# Sheet1.net
KiCad netlist of a schematic drawn in Altium Designer
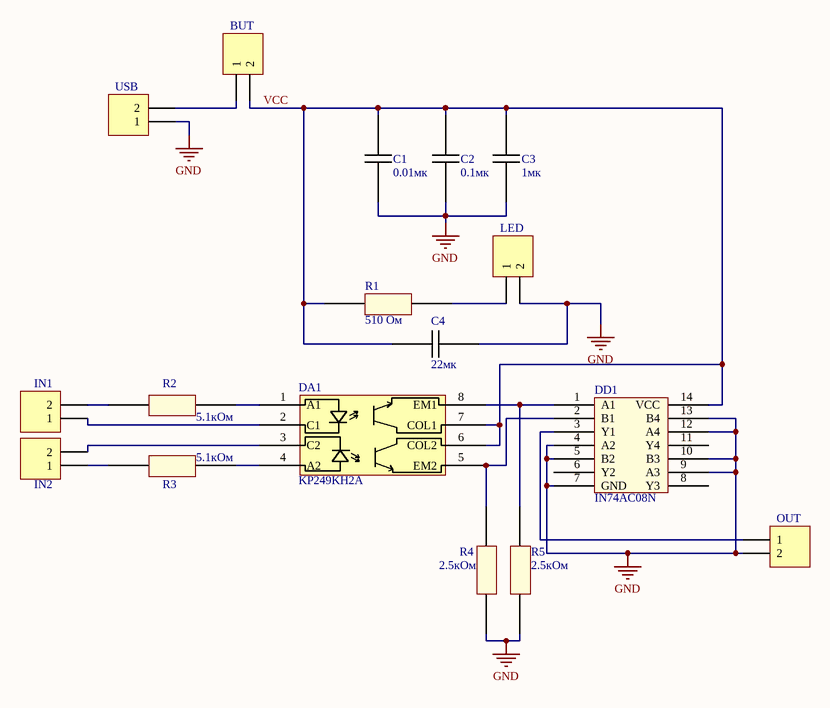
[diagram p0: Sheet1.SchDoc]

(export (version "E")
  (design (tool "Eeschema 10.0.6"))
  (components
    (comp (ref "C1") (value "0.01мк") (footprint "RES 0805") (libsource (lib "msp_SchLib") (part "CAP")))
    (comp (ref "C2") (value "0.1мк") (footprint "RES 0805") (libsource (lib "msp_SchLib") (part "CAP")))
    (comp (ref "C3") (value "1мк") (footprint "RES 0805") (libsource (lib "msp_SchLib") (part "CAP")))
    (comp (ref "C4") (value "22мк") (footprint "RES 0805") (libsource (lib "msp_SchLib") (part "CAP")))
    (comp (ref "DA1")
      (value "KP249KH2A")
      (footprint "SCS-8")
      (libsource (lib "msp_SchLib") (part "KP249KH2A"))
    )
    (comp (ref "DD1")
      (value "IN74AC08N")
      (footprint "SCS-14")
      (libsource (lib "msp_SchLib") (part "IN74AC08N"))
    )
    (comp (ref "P1")
      (value "BUT")
      (footprint "HDR1X2")
      (description "Header, 2-Pin")
      (fields (field (name "PUBLISHER") "Altium Limited"))
      (libsource (lib "Miscellaneous Connectors") (part "Header 2"))
    )
    (comp (ref "P2")
      (value "USB")
      (footprint "HDR1X2")
      (description "Header, 2-Pin")
      (fields (field (name "PUBLISHER") "Altium Limited"))
      (libsource (lib "") (part "Header 2_1"))
    )
    (comp (ref "P3")
      (value "LED")
      (footprint "HDR1X2")
      (description "Header, 2-Pin")
      (fields (field (name "PUBLISHER") "Altium Limited"))
      (libsource (lib "Miscellaneous Connectors") (part "Header 2"))
    )
    (comp (ref "P4")
      (value "IN2")
      (footprint "HDR1X2")
      (description "Header, 2-Pin")
      (fields (field (name "PUBLISHER") "Altium Limited"))
      (libsource (lib "") (part "Header 2_1"))
    )
    (comp (ref "P5")
      (value "IN1")
      (footprint "HDR1X2")
      (description "Header, 2-Pin")
      (fields (field (name "PUBLISHER") "Altium Limited"))
      (libsource (lib "") (part "Header 2_1"))
    )
    (comp (ref "P6")
      (value "OUT")
      (footprint "HDR1X2")
      (description "Header, 2-Pin")
      (fields (field (name "PUBLISHER") "Altium Limited"))
      (libsource (lib "") (part "Header 2_2"))
    )
    (comp (ref "R1") (value "510 Ом") (footprint "RES 0805") (libsource (lib "msp_SchLib") (part "RES")))
    (comp (ref "R2") (value "5.1кОм") (footprint "RES 0805") (libsource (lib "msp_SchLib") (part "RES")))
    (comp (ref "R3") (value "5.1кОм") (footprint "RES 0805") (libsource (lib "msp_SchLib") (part "RES")))
    (comp (ref "R4") (value "2.5кОм") (footprint "RES 0805") (libsource (lib "") (part "RES_1")))
    (comp (ref "R5") (value "2.5кОм") (footprint "RES 0805") (libsource (lib "") (part "RES_1")))
  )
  (nets
    (net (code "1") (name "/VCC") (class "Default")
      (node (ref "C1") (pin "2") (pinfunction "2_2") (pintype "passive"))
      (node (ref "C2") (pin "2") (pinfunction "2_2") (pintype "passive"))
      (node (ref "C3") (pin "2") (pinfunction "2_2") (pintype "passive"))
      (node (ref "C4") (pin "2") (pinfunction "2_2") (pintype "passive"))
      (node (ref "DA1") (pin "6") (pinfunction "COL2_6") (pintype "passive"))
      (node (ref "DA1") (pin "7") (pinfunction "COL1_7") (pintype "passive"))
      (node (ref "DD1") (pin "14") (pinfunction "VCC_14") (pintype "passive"))
      (node (ref "P1") (pin "2") (pinfunction "2_2") (pintype "passive"))
      (node (ref "R1") (pin "1") (pinfunction "1_1") (pintype "passive"))
    )
    (net (code "2") (name "GND") (class "Default")
      (node (ref "C1") (pin "1") (pinfunction "1_1") (pintype "passive"))
      (node (ref "C2") (pin "1") (pinfunction "1_1") (pintype "passive"))
      (node (ref "C3") (pin "1") (pinfunction "1_1") (pintype "passive"))
      (node (ref "C4") (pin "1") (pinfunction "1_1") (pintype "passive"))
      (node (ref "DD1") (pin "10") (pinfunction "B3_10") (pintype "passive"))
      (node (ref "DD1") (pin "12") (pinfunction "A4_12") (pintype "passive"))
      (node (ref "DD1") (pin "13") (pinfunction "B4_13") (pintype "passive"))
      (node (ref "DD1") (pin "4") (pinfunction "A2_4") (pintype "passive"))
      (node (ref "DD1") (pin "5") (pinfunction "B2_5") (pintype "passive"))
      (node (ref "DD1") (pin "7") (pinfunction "GND_7") (pintype "passive"))
      (node (ref "DD1") (pin "9") (pinfunction "A3_9") (pintype "passive"))
      (node (ref "P2") (pin "1") (pinfunction "1_1") (pintype "passive"))
      (node (ref "P3") (pin "2") (pinfunction "2_2") (pintype "passive"))
      (node (ref "P6") (pin "2") (pinfunction "2_2") (pintype "passive"))
      (node (ref "R4") (pin "1") (pinfunction "1_1") (pintype "passive"))
      (node (ref "R5") (pin "1") (pinfunction "1_1") (pintype "passive"))
    )
    (net (code "3") (name "Net-(DA1-A1)") (class "Default")
      (node (ref "DA1") (pin "1") (pinfunction "A1_1") (pintype "passive"))
      (node (ref "R2") (pin "2") (pinfunction "2_2") (pintype "passive"))
    )
    (net (code "4") (name "Net-(DA1-A2)") (class "Default")
      (node (ref "DA1") (pin "4") (pinfunction "A2_4") (pintype "passive"))
      (node (ref "R3") (pin "2") (pinfunction "2_2") (pintype "passive"))
    )
    (net (code "5") (name "Net-(DA1-C1)") (class "Default")
      (node (ref "DA1") (pin "2") (pinfunction "C1_2") (pintype "passive"))
      (node (ref "P5") (pin "1") (pinfunction "1_1") (pintype "passive"))
    )
    (net (code "6") (name "Net-(DA1-C2)") (class "Default")
      (node (ref "DA1") (pin "3") (pinfunction "C2_3") (pintype "passive"))
      (node (ref "P4") (pin "2") (pinfunction "2_2") (pintype "passive"))
    )
    (net (code "7") (name "Net-(DA1-EM1)") (class "Default")
      (node (ref "DA1") (pin "8") (pinfunction "EM1_8") (pintype "passive"))
      (node (ref "DD1") (pin "1") (pinfunction "A1_1") (pintype "passive"))
      (node (ref "R5") (pin "2") (pinfunction "2_2") (pintype "passive"))
    )
    (net (code "8") (name "Net-(DA1-EM2)") (class "Default")
      (node (ref "DA1") (pin "5") (pinfunction "EM2_5") (pintype "passive"))
      (node (ref "DD1") (pin "2") (pinfunction "B1_2") (pintype "passive"))
      (node (ref "R4") (pin "2") (pinfunction "2_2") (pintype "passive"))
    )
    (net (code "9") (name "Net-(DD1-Y1)") (class "Default")
      (node (ref "DD1") (pin "3") (pinfunction "Y1_3") (pintype "passive"))
      (node (ref "P6") (pin "1") (pinfunction "1_1") (pintype "passive"))
    )
    (net (code "10") (name "Net-(P1-Pad1)") (class "Default")
      (node (ref "P1") (pin "1") (pinfunction "1_1") (pintype "passive"))
      (node (ref "P2") (pin "2") (pinfunction "2_2") (pintype "passive"))
    )
    (net (code "11") (name "Net-(P3-Pad1)") (class "Default")
      (node (ref "P3") (pin "1") (pinfunction "1_1") (pintype "passive"))
      (node (ref "R1") (pin "2") (pinfunction "2_2") (pintype "passive"))
    )
    (net (code "12") (name "Net-(P4-Pad1)") (class "Default")
      (node (ref "P4") (pin "1") (pinfunction "1_1") (pintype "passive"))
      (node (ref "R3") (pin "1") (pinfunction "1_1") (pintype "passive"))
    )
    (net (code "13") (name "Net-(P5-Pad2)") (class "Default")
      (node (ref "P5") (pin "2") (pinfunction "2_2") (pintype "passive"))
      (node (ref "R2") (pin "1") (pinfunction "1_1") (pintype "passive"))
    )
    (net (code "14") (name "unconnected-(DD1-Y2-Pad6)") (class "Default")
      (node (ref "DD1") (pin "6") (pinfunction "Y2_6") (pintype "passive"))
    )
    (net (code "15") (name "unconnected-(DD1-Y3-Pad8)") (class "Default")
      (node (ref "DD1") (pin "8") (pinfunction "Y3_8") (pintype "passive"))
    )
    (net (code "16") (name "unconnected-(DD1-Y4-Pad11)") (class "Default")
      (node (ref "DD1") (pin "11") (pinfunction "Y4_11") (pintype "passive"))
    )
  )
)
